# PACE.net
KiCad netlist of a schematic drawn in EAGLE
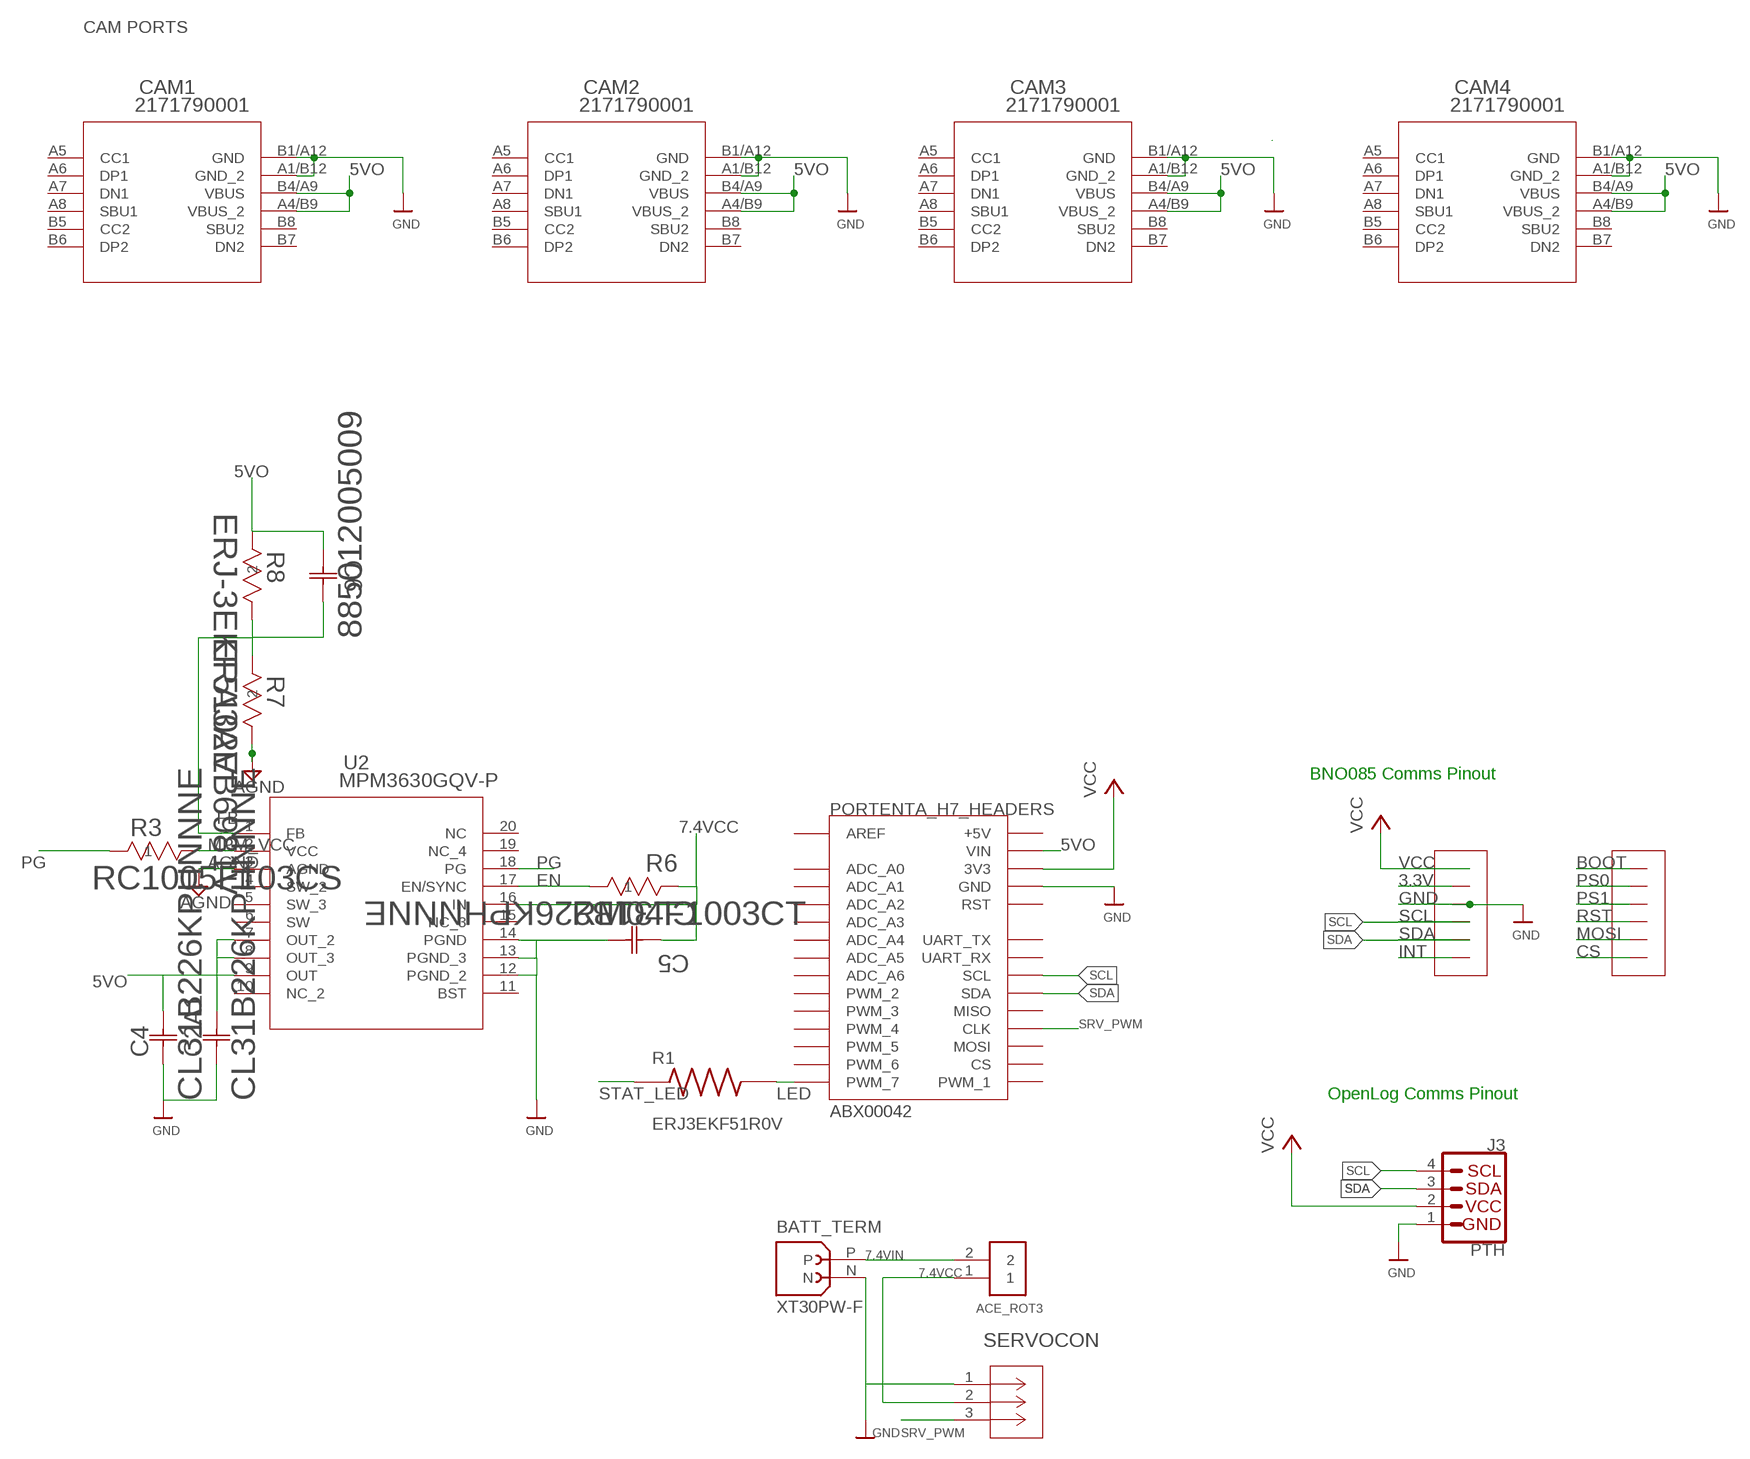
[diagram p0: schematic, sheet 1]
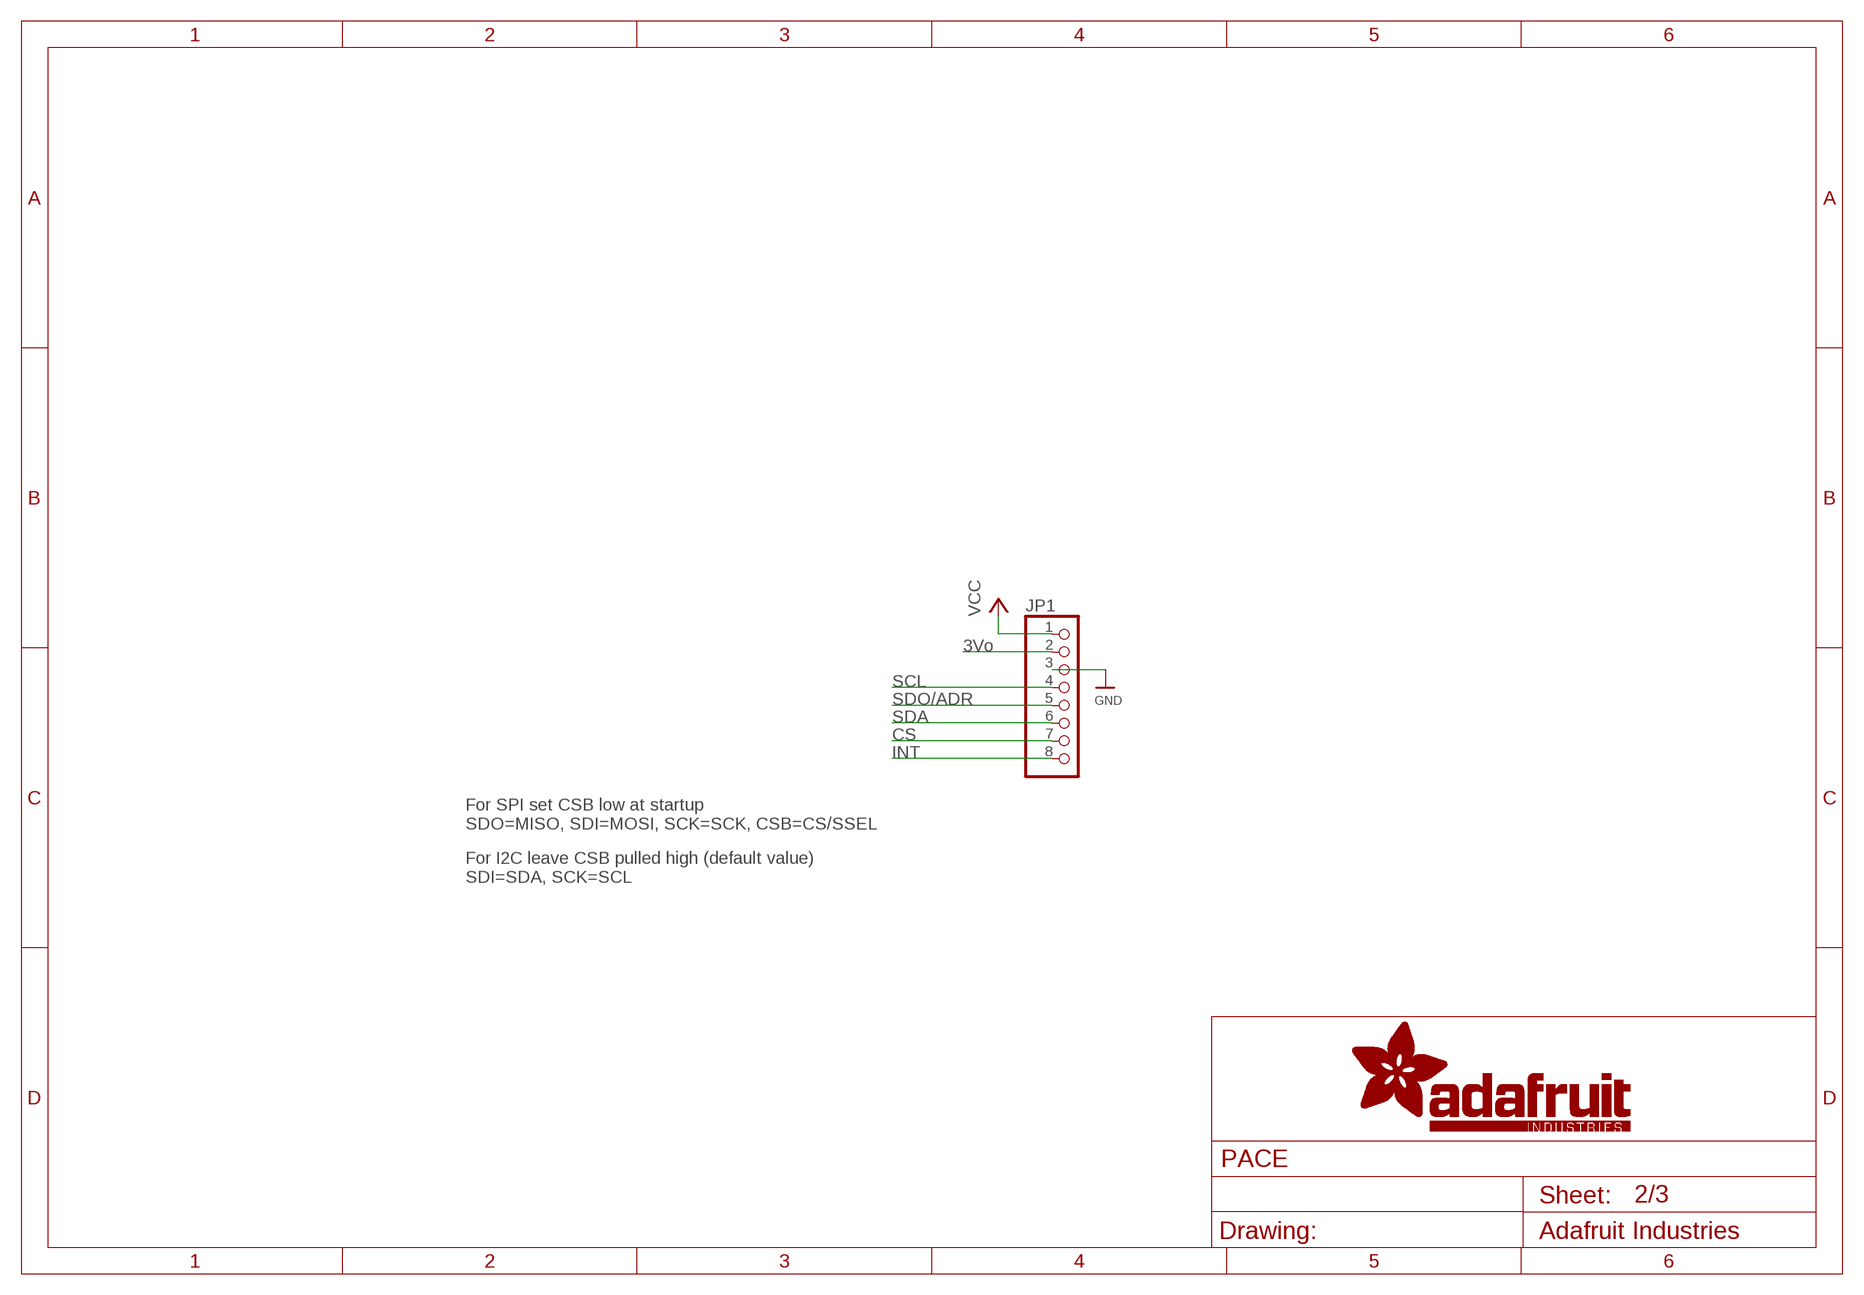
[diagram p1: schematic, sheet 2]
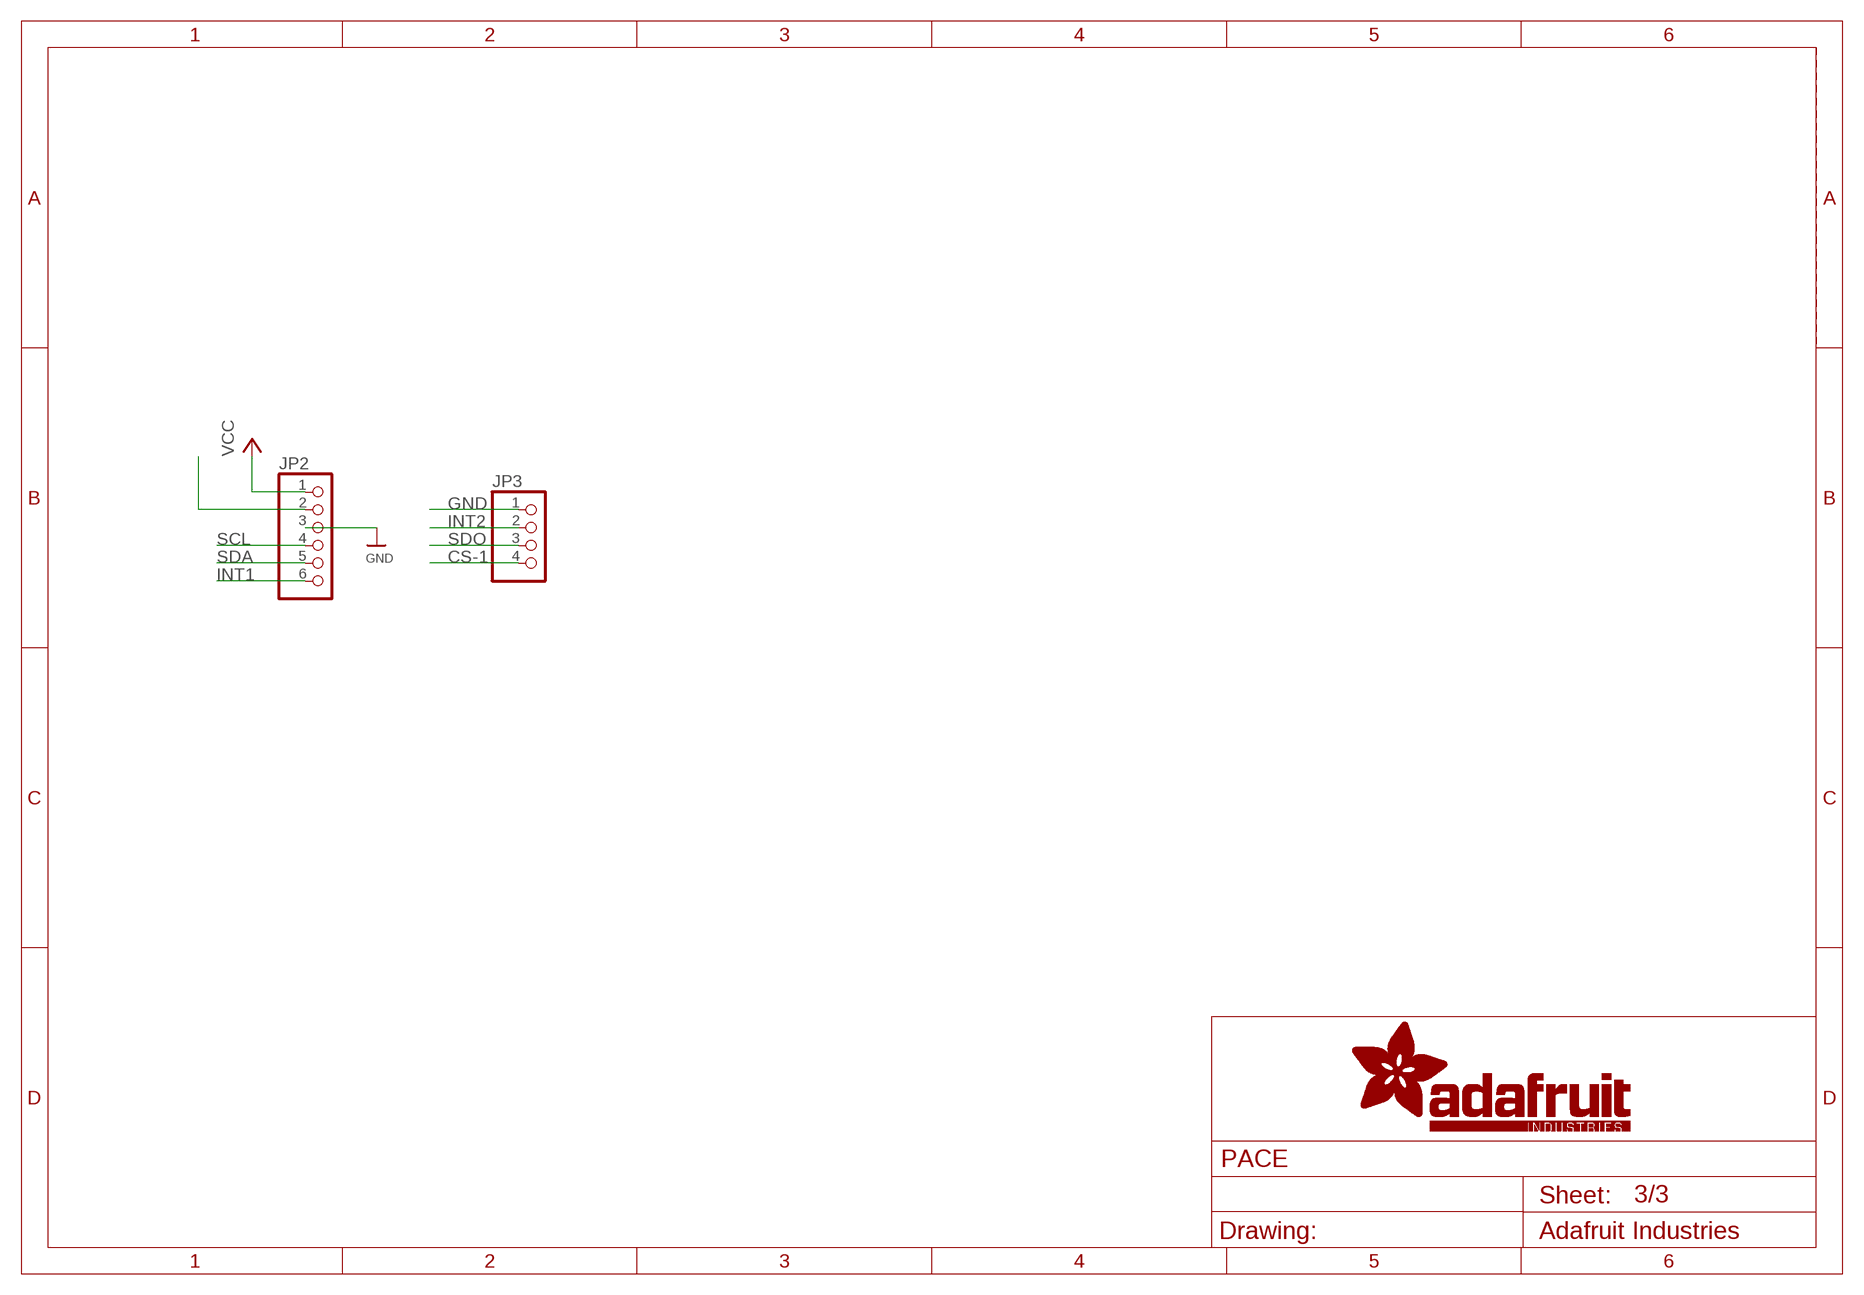
[diagram p2: schematic, sheet 3]

(export (version "E")
  (design (tool "Eeschema 10.0.6"))
  (components
    (comp (ref "JP2")
      (value "HEADER-1X670MIL")
      (footprint "eagle-import:1X06_ROUND_70")
      (libsource (lib "eagle-import") (part "HEADER-1X670MIL"))
    )
    (comp (ref "JP3")
      (value "HEADER-1X4ROUND")
      (footprint "eagle-import:1X04_ROUND")
      (libsource (lib "eagle-import") (part "HEADER-1X4ROUND"))
    )
    (comp (ref "JP1")
      (value "HEADER-1X870MIL")
      (footprint "eagle-import:1X08_ROUND_70")
      (libsource (lib "eagle-import") (part "HEADER-1X870MIL"))
    )
    (comp (ref "ACE_ROT3")
      (value "282837-2")
      (footprint "eagle-import:TE_282837-2")
      (fields (field (name "MF") "TE Connectivity"))
      (libsource (lib "eagle-import") (part "282837-2"))
    )
    (comp (ref "BATT_TERM")
      (value "XT30PW-F")
      (footprint "eagle-import:AMASS_XT30PW-F")
      (fields (field (name "MF") "amass"))
      (libsource (lib "eagle-import") (part "XT30PW-F"))
    )
    (comp (ref "C2A1")
      (value "CL31B226KPHNNNE")
      (footprint "eagle-import:CAP_CL31_SAM")
      (fields (field (name "COPYRIGHT") "Copyright (C) 2024 Ultra Librarian. All rights reserved."))
      (libsource (lib "eagle-import") (part "CL31B226KPHNNNE"))
    )
    (comp (ref "C4")
      (value "CL31B226KPHNNNE")
      (footprint "eagle-import:CAP_CL31_SAM")
      (fields (field (name "COPYRIGHT") "Copyright (C) 2024 Ultra Librarian. All rights reserved."))
      (libsource (lib "eagle-import") (part "CL31B226KPHNNNE"))
    )
    (comp (ref "C5")
      (value "CL31B226KPHNNNE")
      (footprint "eagle-import:CAP_CL31_SAM")
      (fields (field (name "COPYRIGHT") "Copyright (C) 2024 Ultra Librarian. All rights reserved."))
      (libsource (lib "eagle-import") (part "CL31B226KPHNNNE"))
    )
    (comp (ref "C6")
      (value "885012005009")
      (footprint "eagle-import:CAP_885012005_WRE")
      (fields (field (name "COPYRIGHT") "Copyright (C) 2024 Ultra Librarian. All rights reserved."))
      (libsource (lib "eagle-import") (part "885012005009"))
    )
    (comp (ref "CAM1")
      (value "2171790001")
      (footprint "eagle-import:2171790001_MOL")
      (fields (field (name "COPYRIGHT") "Copyright (C) 2024 Ultra Librarian. All rights reserved."))
      (libsource (lib "eagle-import") (part "2171790001"))
    )
    (comp (ref "CAM2")
      (value "2171790001")
      (footprint "eagle-import:2171790001_MOL")
      (fields (field (name "COPYRIGHT") "Copyright (C) 2024 Ultra Librarian. All rights reserved."))
      (libsource (lib "eagle-import") (part "2171790001"))
    )
    (comp (ref "CAM3")
      (value "2171790001")
      (footprint "eagle-import:2171790001_MOL")
      (fields (field (name "COPYRIGHT") "Copyright (C) 2024 Ultra Librarian. All rights reserved."))
      (libsource (lib "eagle-import") (part "2171790001"))
    )
    (comp (ref "CAM4")
      (value "2171790001")
      (footprint "eagle-import:2171790001_MOL")
      (fields (field (name "COPYRIGHT") "Copyright (C) 2024 Ultra Librarian. All rights reserved."))
      (libsource (lib "eagle-import") (part "2171790001"))
    )
    (comp (ref "J3")
      (value "PTH")
      (footprint "eagle-import:1X04_NO_SILK")
      (libsource (lib "eagle-import") (part "I2C_STANDARD_NO_SILK"))
    )
    (comp (ref "R1")
      (value "ERJ3EKF51R0V")
      (footprint "eagle-import:RES_ERJ3EKF51R0V")
      (fields (field (name "MANUFACTURER") "Panasonic"))
      (libsource (lib "eagle-import") (part "ERJ3EKF51R0V"))
    )
    (comp (ref "R3")
      (value "RC1005F103CS")
      (footprint "eagle-import:RES_1005_SAM")
      (fields (field (name "COPYRIGHT") "Copyright (C) 2024 Ultra Librarian. All rights reserved."))
      (libsource (lib "eagle-import") (part "RC1005F103CS"))
    )
    (comp (ref "R6")
      (value "RM04F1003CT")
      (footprint "eagle-import:RES_RM04_CCE")
      (fields (field (name "COPYRIGHT") "Copyright (C) 2024 Ultra Librarian. All rights reserved."))
      (libsource (lib "eagle-import") (part "RM04F1003CT"))
    )
    (comp (ref "R7")
      (value "ERA3AEB6981V")
      (footprint "eagle-import:RES_ERA3A_0603_PAN")
      (fields (field (name "COPYRIGHT") "Copyright (C) 2024 Ultra Librarian. All rights reserved."))
      (libsource (lib "eagle-import") (part "ERA3AEB6981V"))
    )
    (comp (ref "R8")
      (value "ERJ-3EKF5102V")
      (footprint "eagle-import:RC0603N_PAN")
      (fields (field (name "COPYRIGHT") "Copyright (C) 2024 Ultra Librarian. All rights reserved."))
      (libsource (lib "eagle-import") (part "ERJ-3EKF5102V"))
    )
    (comp (ref "SERVOCON")
      (value "B03B-PASK-1_(LF)_(SN)")
      (footprint "eagle-import:CONN_B03B-PASK-1_(LF)_(SN)_JST")
      (fields
        (field (name "MANUFACTURER_PART_NUMBER") "B03B-PASK-1 (LF) (SN)")
        (field (name "COPYRIGHT") "Copyright (C) 2024 Ultra Librarian. All rights reserved.")
      )
      (libsource (lib "eagle-import") (part "B03B-PASK-1_(LF)_(SN)"))
    )
    (comp (ref "U$5")
      (value "ADAFRUIT_BNO08X")
      (footprint "eagle-import:ADAFRUIT_BNO08X_FOOTPRINT")
      (libsource (lib "eagle-import") (part "ADAFRUIT_BNO08X"))
    )
    (comp (ref "U$10")
      (value "ABX00042_HEADERS_IO")
      (footprint "eagle-import:MODULE_ABX00042_HEADERS")
      (libsource (lib "eagle-import") (part "ABX00042_HEADERS_IO"))
    )
    (comp (ref "U2")
      (value "MPM3630GQV-P")
      (footprint "eagle-import:QFN3P0X5P0X1P6_MPM3630_MNP")
      (fields (field (name "COPYRIGHT") "Copyright (C) 2024 Ultra Librarian. All rights reserved."))
      (libsource (lib "eagle-import") (part "MPM3630GQV-P"))
    )
  )
  (nets
    (net (code "1") (name "5VO") (class "Default")
      (node (ref "C2A1") (pin "2") (pinfunction "2_2") (pintype "passive"))
      (node (ref "C4") (pin "2") (pinfunction "2_2") (pintype "passive"))
      (node (ref "C6") (pin "2") (pinfunction "2_2") (pintype "passive"))
      (node (ref "CAM1") (pin "A4/B9") (pinfunction "VBUS_2_A4/B9") (pintype "power_in"))
      (node (ref "CAM1") (pin "B4/A9") (pinfunction "VBUS_B4/A9") (pintype "power_in"))
      (node (ref "CAM2") (pin "A4/B9") (pinfunction "VBUS_2_A4/B9") (pintype "power_in"))
      (node (ref "CAM2") (pin "B4/A9") (pinfunction "VBUS_B4/A9") (pintype "power_in"))
      (node (ref "CAM3") (pin "A4/B9") (pinfunction "VBUS_2_A4/B9") (pintype "power_in"))
      (node (ref "CAM3") (pin "B4/A9") (pinfunction "VBUS_B4/A9") (pintype "power_in"))
      (node (ref "CAM4") (pin "A4/B9") (pinfunction "VBUS_2_A4/B9") (pintype "power_in"))
      (node (ref "CAM4") (pin "B4/A9") (pinfunction "VBUS_B4/A9") (pintype "power_in"))
      (node (ref "R8") (pin "2") (pinfunction "2_2") (pintype "passive"))
      (node (ref "U$10") (pin "J16") (pinfunction "VIN_J16") (pintype "bidirectional"))
      (node (ref "U2") (pin "7") (pinfunction "OUT_2_7") (pintype "output"))
      (node (ref "U2") (pin "8") (pinfunction "OUT_3_8") (pintype "output"))
      (node (ref "U2") (pin "9") (pinfunction "OUT_9") (pintype "output"))
    )
    (net (code "2") (name "7.4VCC") (class "Default")
      (node (ref "ACE_ROT3") (pin "1") (pinfunction "1_1") (pintype "passive"))
      (node (ref "C5") (pin "1") (pinfunction "1_1") (pintype "passive"))
      (node (ref "R6") (pin "2") (pinfunction "2_2") (pintype "passive"))
      (node (ref "SERVOCON") (pin "2") (pinfunction "2_2") (pintype "passive"))
      (node (ref "U2") (pin "16") (pinfunction "IN_16") (pintype "power_in"))
    )
    (net (code "3") (name "7.4VIN") (class "Default")
      (node (ref "ACE_ROT3") (pin "2") (pinfunction "2_2") (pintype "passive"))
      (node (ref "BATT_TERM") (pin "P") (pinfunction "P_P") (pintype "power_in"))
    )
    (net (code "4") (name "AGND") (class "Default")
      (node (ref "R7") (pin "1") (pinfunction "1_1") (pintype "passive"))
      (node (ref "U2") (pin "3") (pinfunction "AGND_3") (pintype "passive"))
    )
    (net (code "5") (name "CS") (class "Default")
      (node (ref "JP1") (pin "7") (pinfunction "7_7") (pintype "passive"))
    )
    (net (code "6") (name "CS-1") (class "Default")
      (node (ref "JP3") (pin "4") (pinfunction "4_4") (pintype "passive"))
    )
    (net (code "7") (name "EN") (class "Default")
      (node (ref "R6") (pin "1") (pinfunction "1_1") (pintype "passive"))
      (node (ref "U2") (pin "17") (pinfunction "EN/SYNC_17") (pintype "passive"))
    )
    (net (code "8") (name "FB") (class "Default")
      (node (ref "C6") (pin "1") (pinfunction "1_1") (pintype "passive"))
      (node (ref "R7") (pin "2") (pinfunction "2_2") (pintype "passive"))
      (node (ref "R8") (pin "1") (pinfunction "1_1") (pintype "passive"))
      (node (ref "U2") (pin "1") (pinfunction "FB_1") (pintype "input"))
    )
    (net (code "9") (name "GND") (class "Default")
      (node (ref "BATT_TERM") (pin "N") (pinfunction "N_N") (pintype "power_in"))
      (node (ref "C2A1") (pin "1") (pinfunction "1_1") (pintype "passive"))
      (node (ref "C4") (pin "1") (pinfunction "1_1") (pintype "passive"))
      (node (ref "C5") (pin "2") (pinfunction "2_2") (pintype "passive"))
      (node (ref "CAM1") (pin "A1/B12") (pinfunction "GND_2_A1/B12") (pintype "passive"))
      (node (ref "CAM1") (pin "B1/A12") (pinfunction "GND_B1/A12") (pintype "passive"))
      (node (ref "CAM2") (pin "A1/B12") (pinfunction "GND_2_A1/B12") (pintype "passive"))
      (node (ref "CAM2") (pin "B1/A12") (pinfunction "GND_B1/A12") (pintype "passive"))
      (node (ref "CAM3") (pin "A1/B12") (pinfunction "GND_2_A1/B12") (pintype "passive"))
      (node (ref "CAM3") (pin "B1/A12") (pinfunction "GND_B1/A12") (pintype "passive"))
      (node (ref "CAM4") (pin "A1/B12") (pinfunction "GND_2_A1/B12") (pintype "passive"))
      (node (ref "CAM4") (pin "B1/A12") (pinfunction "GND_B1/A12") (pintype "passive"))
      (node (ref "J3") (pin "1") (pinfunction "GND_1") (pintype "power_in"))
      (node (ref "JP1") (pin "3") (pinfunction "3_3") (pintype "passive"))
      (node (ref "JP2") (pin "3") (pinfunction "3_3") (pintype "passive"))
      (node (ref "JP3") (pin "1") (pinfunction "1_1") (pintype "passive"))
      (node (ref "SERVOCON") (pin "1") (pinfunction "1_1") (pintype "passive"))
      (node (ref "U$10") (pin "J18") (pinfunction "GND_J18") (pintype "bidirectional"))
      (node (ref "U$5") (pin "GND") (pinfunction "GND_GND") (pintype "bidirectional"))
      (node (ref "U2") (pin "12") (pinfunction "PGND_2_12") (pintype "passive"))
      (node (ref "U2") (pin "13") (pinfunction "PGND_3_13") (pintype "passive"))
      (node (ref "U2") (pin "14") (pinfunction "PGND_14") (pintype "passive"))
    )
    (net (code "10") (name "INT") (class "Default")
      (node (ref "JP1") (pin "8") (pinfunction "8_8") (pintype "passive"))
    )
    (net (code "11") (name "INT1") (class "Default")
      (node (ref "JP2") (pin "6") (pinfunction "6_6") (pintype "passive"))
    )
    (net (code "12") (name "INT2") (class "Default")
      (node (ref "JP3") (pin "2") (pinfunction "2_2") (pintype "passive"))
    )
    (net (code "13") (name "LED") (class "Default")
      (node (ref "R1") (pin "2") (pinfunction "2_2") (pintype "passive"))
      (node (ref "U$10") (pin "J9") (pinfunction "PWM_7_J9") (pintype "bidirectional"))
    )
    (net (code "14") (name "MPM_VCC") (class "Default")
      (node (ref "R3") (pin "2") (pinfunction "2_2") (pintype "passive"))
      (node (ref "U2") (pin "2") (pinfunction "VCC_2") (pintype "power_in"))
    )
    (net (code "15") (name "PG") (class "Default")
      (node (ref "R3") (pin "1") (pinfunction "1_1") (pintype "passive"))
      (node (ref "U2") (pin "18") (pinfunction "PG_18") (pintype "passive"))
    )
    (net (code "16") (name "SCL") (class "Default")
      (node (ref "J3") (pin "4") (pinfunction "SCL_4") (pintype "passive"))
      (node (ref "JP1") (pin "4") (pinfunction "4_4") (pintype "passive"))
      (node (ref "JP2") (pin "4") (pinfunction "4_4") (pintype "passive"))
      (node (ref "U$10") (pin "J22") (pinfunction "SCL_J22") (pintype "bidirectional"))
      (node (ref "U$5") (pin "SCL") (pinfunction "SCL_SCL") (pintype "bidirectional"))
    )
    (net (code "17") (name "SDA") (class "Default")
      (node (ref "J3") (pin "3") (pinfunction "SDA_3") (pintype "passive"))
      (node (ref "JP1") (pin "6") (pinfunction "6_6") (pintype "passive"))
      (node (ref "JP2") (pin "5") (pinfunction "5_5") (pintype "passive"))
      (node (ref "U$10") (pin "J23") (pinfunction "SDA_J23") (pintype "bidirectional"))
      (node (ref "U$5") (pin "SDA") (pinfunction "SDA_SDA") (pintype "bidirectional"))
    )
    (net (code "18") (name "SDO") (class "Default")
      (node (ref "JP3") (pin "3") (pinfunction "3_3") (pintype "passive"))
    )
    (net (code "19") (name "SDO{slash}ADR") (class "Default")
      (node (ref "JP1") (pin "5") (pinfunction "5_5") (pintype "passive"))
    )
    (net (code "20") (name "SRV_PWM") (class "Default")
      (node (ref "SERVOCON") (pin "3") (pinfunction "3_3") (pintype "passive"))
      (node (ref "U$10") (pin "J25") (pinfunction "CLK_J25") (pintype "bidirectional"))
    )
    (net (code "21") (name "STAT_LED") (class "Default")
      (node (ref "R1") (pin "1") (pinfunction "1_1") (pintype "passive"))
    )
    (net (code "22") (name "VCC") (class "Default")
      (node (ref "J3") (pin "2") (pinfunction "VCC_2") (pintype "power_in"))
      (node (ref "JP1") (pin "1") (pinfunction "1_1") (pintype "passive"))
      (node (ref "JP2") (pin "1") (pinfunction "1_1") (pintype "passive"))
      (node (ref "U$10") (pin "J17") (pinfunction "3V3_J17") (pintype "bidirectional"))
      (node (ref "U$5") (pin "VIN") (pinfunction "VCC_VIN") (pintype "bidirectional"))
    )
    (net (code "23") (name "unconnected-(CAM1-CC1-PadA5)") (class "Default")
      (node (ref "CAM1") (pin "A5") (pinfunction "CC1_A5") (pintype "bidirectional"))
    )
    (net (code "24") (name "unconnected-(CAM1-CC2-PadB5)") (class "Default")
      (node (ref "CAM1") (pin "B5") (pinfunction "CC2_B5") (pintype "bidirectional"))
    )
    (net (code "25") (name "unconnected-(CAM1-DN1-PadA7)") (class "Default")
      (node (ref "CAM1") (pin "A7") (pinfunction "DN1_A7") (pintype "bidirectional"))
    )
    (net (code "26") (name "unconnected-(CAM1-DN2-PadB7)") (class "Default")
      (node (ref "CAM1") (pin "B7") (pinfunction "DN2_B7") (pintype "bidirectional"))
    )
    (net (code "27") (name "unconnected-(CAM1-DP1-PadA6)") (class "Default")
      (node (ref "CAM1") (pin "A6") (pinfunction "DP1_A6") (pintype "bidirectional"))
    )
    (net (code "28") (name "unconnected-(CAM1-DP2-PadB6)") (class "Default")
      (node (ref "CAM1") (pin "B6") (pinfunction "DP2_B6") (pintype "bidirectional"))
    )
    (net (code "29") (name "unconnected-(CAM1-SBU1-PadA8)") (class "Default")
      (node (ref "CAM1") (pin "A8") (pinfunction "SBU1_A8") (pintype "bidirectional"))
    )
    (net (code "30") (name "unconnected-(CAM1-SBU2-PadB8)") (class "Default")
      (node (ref "CAM1") (pin "B8") (pinfunction "SBU2_B8") (pintype "bidirectional"))
    )
    (net (code "31") (name "unconnected-(CAM2-CC1-PadA5)") (class "Default")
      (node (ref "CAM2") (pin "A5") (pinfunction "CC1_A5") (pintype "bidirectional"))
    )
    (net (code "32") (name "unconnected-(CAM2-CC2-PadB5)") (class "Default")
      (node (ref "CAM2") (pin "B5") (pinfunction "CC2_B5") (pintype "bidirectional"))
    )
    (net (code "33") (name "unconnected-(CAM2-DN1-PadA7)") (class "Default")
      (node (ref "CAM2") (pin "A7") (pinfunction "DN1_A7") (pintype "bidirectional"))
    )
    (net (code "34") (name "unconnected-(CAM2-DN2-PadB7)") (class "Default")
      (node (ref "CAM2") (pin "B7") (pinfunction "DN2_B7") (pintype "bidirectional"))
    )
    (net (code "35") (name "unconnected-(CAM2-DP1-PadA6)") (class "Default")
      (node (ref "CAM2") (pin "A6") (pinfunction "DP1_A6") (pintype "bidirectional"))
    )
    (net (code "36") (name "unconnected-(CAM2-DP2-PadB6)") (class "Default")
      (node (ref "CAM2") (pin "B6") (pinfunction "DP2_B6") (pintype "bidirectional"))
    )
    (net (code "37") (name "unconnected-(CAM2-SBU1-PadA8)") (class "Default")
      (node (ref "CAM2") (pin "A8") (pinfunction "SBU1_A8") (pintype "bidirectional"))
    )
    (net (code "38") (name "unconnected-(CAM2-SBU2-PadB8)") (class "Default")
      (node (ref "CAM2") (pin "B8") (pinfunction "SBU2_B8") (pintype "bidirectional"))
    )
    (net (code "39") (name "unconnected-(CAM3-CC1-PadA5)") (class "Default")
      (node (ref "CAM3") (pin "A5") (pinfunction "CC1_A5") (pintype "bidirectional"))
    )
    (net (code "40") (name "unconnected-(CAM3-CC2-PadB5)") (class "Default")
      (node (ref "CAM3") (pin "B5") (pinfunction "CC2_B5") (pintype "bidirectional"))
    )
    (net (code "41") (name "unconnected-(CAM3-DN1-PadA7)") (class "Default")
      (node (ref "CAM3") (pin "A7") (pinfunction "DN1_A7") (pintype "bidirectional"))
    )
    (net (code "42") (name "unconnected-(CAM3-DN2-PadB7)") (class "Default")
      (node (ref "CAM3") (pin "B7") (pinfunction "DN2_B7") (pintype "bidirectional"))
    )
    (net (code "43") (name "unconnected-(CAM3-DP1-PadA6)") (class "Default")
      (node (ref "CAM3") (pin "A6") (pinfunction "DP1_A6") (pintype "bidirectional"))
    )
    (net (code "44") (name "unconnected-(CAM3-DP2-PadB6)") (class "Default")
      (node (ref "CAM3") (pin "B6") (pinfunction "DP2_B6") (pintype "bidirectional"))
    )
    (net (code "45") (name "unconnected-(CAM3-SBU1-PadA8)") (class "Default")
      (node (ref "CAM3") (pin "A8") (pinfunction "SBU1_A8") (pintype "bidirectional"))
    )
    (net (code "46") (name "unconnected-(CAM3-SBU2-PadB8)") (class "Default")
      (node (ref "CAM3") (pin "B8") (pinfunction "SBU2_B8") (pintype "bidirectional"))
    )
    (net (code "47") (name "unconnected-(CAM4-CC1-PadA5)") (class "Default")
      (node (ref "CAM4") (pin "A5") (pinfunction "CC1_A5") (pintype "bidirectional"))
    )
    (net (code "48") (name "unconnected-(CAM4-CC2-PadB5)") (class "Default")
      (node (ref "CAM4") (pin "B5") (pinfunction "CC2_B5") (pintype "bidirectional"))
    )
    (net (code "49") (name "unconnected-(CAM4-DN1-PadA7)") (class "Default")
      (node (ref "CAM4") (pin "A7") (pinfunction "DN1_A7") (pintype "bidirectional"))
    )
    (net (code "50") (name "unconnected-(CAM4-DN2-PadB7)") (class "Default")
      (node (ref "CAM4") (pin "B7") (pinfunction "DN2_B7") (pintype "bidirectional"))
    )
    (net (code "51") (name "unconnected-(CAM4-DP1-PadA6)") (class "Default")
      (node (ref "CAM4") (pin "A6") (pinfunction "DP1_A6") (pintype "bidirectional"))
    )
    (net (code "52") (name "unconnected-(CAM4-DP2-PadB6)") (class "Default")
      (node (ref "CAM4") (pin "B6") (pinfunction "DP2_B6") (pintype "bidirectional"))
    )
    (net (code "53") (name "unconnected-(CAM4-SBU1-PadA8)") (class "Default")
      (node (ref "CAM4") (pin "A8") (pinfunction "SBU1_A8") (pintype "bidirectional"))
    )
    (net (code "54") (name "unconnected-(CAM4-SBU2-PadB8)") (class "Default")
      (node (ref "CAM4") (pin "B8") (pinfunction "SBU2_B8") (pintype "bidirectional"))
    )
    (net (code "55") (name "unconnected-(JP1-Pad2)") (class "Default")
      (node (ref "JP1") (pin "2") (pinfunction "2_2") (pintype "passive"))
    )
    (net (code "56") (name "unconnected-(JP2-Pad2)") (class "Default")
      (node (ref "JP2") (pin "2") (pinfunction "2_2") (pintype "passive"))
    )
    (net (code "57") (name "unconnected-(U$5-3.3V-Pad3VO)") (class "Default")
      (node (ref "U$5") (pin "3VO") (pinfunction "3.3V_3VO") (pintype "bidirectional"))
    )
    (net (code "58") (name "unconnected-(U$5-BOOT-PadBT)") (class "Default")
      (node (ref "U$5") (pin "BT") (pinfunction "BOOT_BT") (pintype "bidirectional"))
    )
    (net (code "59") (name "unconnected-(U$5-MOSI-PadDI)") (class "Default")
      (node (ref "U$5") (pin "DI") (pinfunction "MOSI_DI") (pintype "bidirectional"))
    )
    (net (code "60") (name "unconnected-(U$5-PS0-PadP0)") (class "Default")
      (node (ref "U$5") (pin "P0") (pinfunction "PS0_P0") (pintype "bidirectional"))
    )
    (net (code "61") (name "unconnected-(U$5-PS1-PadP1)") (class "Default")
      (node (ref "U$5") (pin "P1") (pinfunction "PS1_P1") (pintype "bidirectional"))
    )
    (net (code "62") (name "unconnected-(U$5-PadCS)") (class "Default")
      (node (ref "U$5") (pin "CS") (pinfunction "CS_CS") (pintype "bidirectional"))
    )
    (net (code "63") (name "unconnected-(U$5-PadINT)") (class "Default")
      (node (ref "U$5") (pin "INT") (pinfunction "INT_INT") (pintype "bidirectional"))
    )
    (net (code "64") (name "unconnected-(U$5-PadRST)") (class "Default")
      (node (ref "U$5") (pin "RST") (pinfunction "RST_RST") (pintype "bidirectional"))
    )
    (net (code "65") (name "unconnected-(U$10-+5V-PadJ15)") (class "Default")
      (node (ref "U$10") (pin "J15") (pinfunction "+5V_J15") (pintype "bidirectional"))
    )
    (net (code "66") (name "unconnected-(U$10-ADC_A0-PadJ2)") (class "Default")
      (node (ref "U$10") (pin "J2") (pinfunction "ADC_A0_J2") (pintype "bidirectional"))
    )
    (net (code "67") (name "unconnected-(U$10-ADC_A1-PadJ3)") (class "Default")
      (node (ref "U$10") (pin "J3") (pinfunction "ADC_A1_J3") (pintype "bidirectional"))
    )
    (net (code "68") (name "unconnected-(U$10-ADC_A2-PadJ4)") (class "Default")
      (node (ref "U$10") (pin "J4") (pinfunction "ADC_A2_J4") (pintype "bidirectional"))
    )
    (net (code "69") (name "unconnected-(U$10-ADC_A3-PadJ5)") (class "Default")
      (node (ref "U$10") (pin "J5") (pinfunction "ADC_A3_J5") (pintype "bidirectional"))
    )
    (net (code "70") (name "unconnected-(U$10-ADC_A4-PadJ6)") (class "Default")
      (node (ref "U$10") (pin "J6") (pinfunction "ADC_A4_J6") (pintype "bidirectional"))
    )
    (net (code "71") (name "unconnected-(U$10-ADC_A5-PadJ7)") (class "Default")
      (node (ref "U$10") (pin "J7") (pinfunction "ADC_A5_J7") (pintype "bidirectional"))
    )
    (net (code "72") (name "unconnected-(U$10-ADC_A6-PadJ8)") (class "Default")
      (node (ref "U$10") (pin "J8") (pinfunction "ADC_A6_J8") (pintype "bidirectional"))
    )
    (net (code "73") (name "unconnected-(U$10-AREF-PadJ1)") (class "Default")
      (node (ref "U$10") (pin "J1") (pinfunction "AREF_J1") (pintype "bidirectional"))
    )
    (net (code "74") (name "unconnected-(U$10-CS-PadJ27)") (class "Default")
      (node (ref "U$10") (pin "J27") (pinfunction "CS_J27") (pintype "bidirectional"))
    )
    (net (code "75") (name "unconnected-(U$10-MISO-PadJ24)") (class "Default")
      (node (ref "U$10") (pin "J24") (pinfunction "MISO_J24") (pintype "bidirectional"))
    )
    (net (code "76") (name "unconnected-(U$10-MOSI-PadJ26)") (class "Default")
      (node (ref "U$10") (pin "J26") (pinfunction "MOSI_J26") (pintype "bidirectional"))
    )
    (net (code "77") (name "unconnected-(U$10-PWM_1-PadJ28)") (class "Default")
      (node (ref "U$10") (pin "J28") (pinfunction "PWM_1_J28") (pintype "bidirectional"))
    )
    (net (code "78") (name "unconnected-(U$10-PWM_2-PadJ14)") (class "Default")
      (node (ref "U$10") (pin "J14") (pinfunction "PWM_2_J14") (pintype "bidirectional"))
    )
    (net (code "79") (name "unconnected-(U$10-PWM_3-PadJ13)") (class "Default")
      (node (ref "U$10") (pin "J13") (pinfunction "PWM_3_J13") (pintype "bidirectional"))
    )
    (net (code "80") (name "unconnected-(U$10-PWM_4-PadJ12)") (class "Default")
      (node (ref "U$10") (pin "J12") (pinfunction "PWM_4_J12") (pintype "bidirectional"))
    )
    (net (code "81") (name "unconnected-(U$10-PWM_5-PadJ11)") (class "Default")
      (node (ref "U$10") (pin "J11") (pinfunction "PWM_5_J11") (pintype "bidirectional"))
    )
    (net (code "82") (name "unconnected-(U$10-PWM_6-PadJ10)") (class "Default")
      (node (ref "U$10") (pin "J10") (pinfunction "PWM_6_J10") (pintype "bidirectional"))
    )
    (net (code "83") (name "unconnected-(U$10-RST-PadJ19)") (class "Default")
      (node (ref "U$10") (pin "J19") (pinfunction "RST_J19") (pintype "bidirectional"))
    )
    (net (code "84") (name "unconnected-(U$10-UART_RX-PadJ21)") (class "Default")
      (node (ref "U$10") (pin "J21") (pinfunction "UART_RX_J21") (pintype "bidirectional"))
    )
    (net (code "85") (name "unconnected-(U$10-UART_TX-PadJ20)") (class "Default")
      (node (ref "U$10") (pin "J20") (pinfunction "UART_TX_J20") (pintype "bidirectional"))
    )
    (net (code "86") (name "unconnected-(U2-BST-Pad11)") (class "Default")
      (node (ref "U2") (pin "11") (pinfunction "BST_11") (pintype "passive"))
    )
    (net (code "87") (name "unconnected-(U2-NC-Pad20)") (class "Default")
      (node (ref "U2") (pin "20") (pinfunction "NC_20") (pintype "no_connect"))
    )
    (net (code "88") (name "unconnected-(U2-NC_2-Pad10)") (class "Default")
      (node (ref "U2") (pin "10") (pinfunction "NC_2_10") (pintype "no_connect"))
    )
    (net (code "89") (name "unconnected-(U2-NC_3-Pad15)") (class "Default")
      (node (ref "U2") (pin "15") (pinfunction "NC_3_15") (pintype "no_connect"))
    )
    (net (code "90") (name "unconnected-(U2-NC_4-Pad19)") (class "Default")
      (node (ref "U2") (pin "19") (pinfunction "NC_4_19") (pintype "no_connect"))
    )
    (net (code "91") (name "unconnected-(U2-SW-Pad6)") (class "Default")
      (node (ref "U2") (pin "6") (pinfunction "SW_6") (pintype "output"))
    )
    (net (code "92") (name "unconnected-(U2-SW_2-Pad4)") (class "Default")
      (node (ref "U2") (pin "4") (pinfunction "SW_2_4") (pintype "output"))
    )
    (net (code "93") (name "unconnected-(U2-SW_3-Pad5)") (class "Default")
      (node (ref "U2") (pin "5") (pinfunction "SW_3_5") (pintype "output"))
    )
  )
)
